# Circuit_Diagram.net
KiCad netlist of a schematic drawn in EAGLE
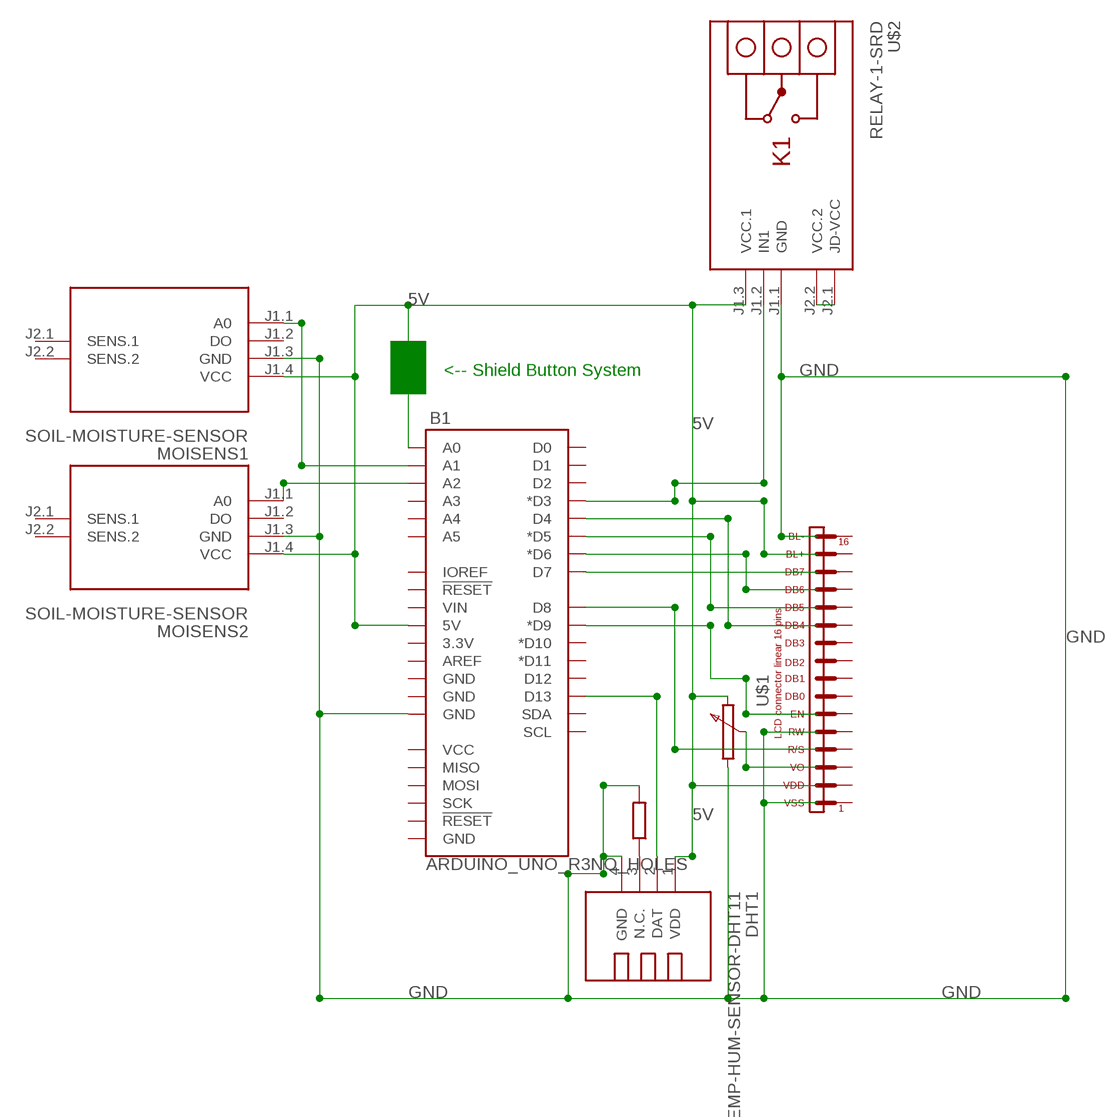
[diagram p0: schematic, sheet 1]

(export (version "E")
  (design (tool "Eeschema 10.0.6"))
  (components
    (comp (ref "B1")
      (value "ARDUINO_UNO_R3NO_HOLES")
      (footprint "eagle-import:ARDUINO_R3_NO_HOLES")
      (libsource (lib "eagle-import") (part "ARDUINO_UNO_R3NO_HOLES"))
    )
    (comp (ref "DHT1")
      (value "TEMP-HUM-SENSOR-DHT11")
      (footprint "eagle-import:TEMP-HUM-SENSOR-DHT11")
      (libsource (lib "eagle-import") (part "TEMP-HUM-SENSOR-DHT11"))
    )
    (comp (ref "MOISENS1")
      (value "SOIL-MOISTURE-SENSOR")
      (footprint "eagle-import:SOIL-MOISTURE-SENSOR")
      (libsource (lib "eagle-import") (part "SOIL-MOISTURE-SENSOR"))
    )
    (comp (ref "MOISENS2")
      (value "SOIL-MOISTURE-SENSOR")
      (footprint "eagle-import:SOIL-MOISTURE-SENSOR")
      (libsource (lib "eagle-import") (part "SOIL-MOISTURE-SENSOR"))
    )
    (comp (ref "U$1")
      (value "-LCD2X16")
      (footprint "eagle-import:CON8X2LCD")
      (libsource (lib "eagle-import") (part "-LCD2X16"))
    )
    (comp (ref "U$2")
      (value "RELAY-1-SRD")
      (footprint "eagle-import:RELAY-1-SRD")
      (libsource (lib "eagle-import") (part "RELAY-1-SRD"))
    )
  )
  (nets
    (net (code "1") (name "/5V") (class "Default")
      (node (ref "B1") (pin "5V") (pinfunction "5V_5V") (pintype "bidirectional"))
      (node (ref "B1") (pin "A0") (pinfunction "A0_A0") (pintype "bidirectional"))
      (node (ref "DHT1") (pin "1") (pinfunction "VDD_1") (pintype "power_in"))
      (node (ref "MOISENS1") (pin "J1.4") (pinfunction "VCC_J1.4") (pintype "power_in"))
      (node (ref "MOISENS2") (pin "J1.4") (pinfunction "VCC_J1.4") (pintype "power_in"))
      (node (ref "U$2") (pin "J1.3") (pinfunction "VCC.1_J1.3") (pintype "power_in"))
    )
    (net (code "2") (name "/GND") (class "Default")
      (node (ref "B1") (pin "GND@2") (pinfunction "GND_GND@2") (pintype "bidirectional"))
      (node (ref "DHT1") (pin "4") (pinfunction "GND_4") (pintype "power_in"))
      (node (ref "MOISENS1") (pin "J1.3") (pinfunction "GND_J1.3") (pintype "power_in"))
      (node (ref "MOISENS2") (pin "J1.3") (pinfunction "GND_J1.3") (pintype "power_in"))
      (node (ref "U$2") (pin "J1.1") (pinfunction "GND_J1.1") (pintype "power_in"))
    )
    (net (code "3") (name "Net-(B1-*D3)") (class "Default")
      (node (ref "B1") (pin "D3") (pinfunction "*D3_D3") (pintype "bidirectional"))
      (node (ref "U$2") (pin "J1.2") (pinfunction "IN1_J1.2") (pintype "bidirectional"))
    )
    (net (code "4") (name "Net-(DHT1-DAT)") (class "Default")
      (node (ref "B1") (pin "D13") (pinfunction "D13_D13") (pintype "bidirectional"))
      (node (ref "DHT1") (pin "2") (pinfunction "DAT_2") (pintype "bidirectional"))
    )
    (net (code "5") (name "Net-(MOISENS1-A0)") (class "Default")
      (node (ref "B1") (pin "A1") (pinfunction "A1_A1") (pintype "bidirectional"))
      (node (ref "MOISENS1") (pin "J1.1") (pinfunction "A0_J1.1") (pintype "bidirectional"))
    )
    (net (code "6") (name "Net-(MOISENS2-A0)") (class "Default")
      (node (ref "B1") (pin "A2") (pinfunction "A2_A2") (pintype "bidirectional"))
      (node (ref "MOISENS2") (pin "J1.1") (pinfunction "A0_J1.1") (pintype "bidirectional"))
    )
    (net (code "7") (name "Net-(U$2-JD-VCC)") (class "Default")
      (node (ref "U$2") (pin "J2.1") (pinfunction "JD-VCC_J2.1") (pintype "bidirectional"))
      (node (ref "U$2") (pin "J2.2") (pinfunction "VCC.2_J2.2") (pintype "power_in"))
    )
    (net (code "8") (name "unconnected-(B1-*D5-PadD5)") (class "Default")
      (node (ref "B1") (pin "D5") (pinfunction "*D5_D5") (pintype "bidirectional"))
    )
    (net (code "9") (name "unconnected-(B1-*D6-PadD6)") (class "Default")
      (node (ref "B1") (pin "D6") (pinfunction "*D6_D6") (pintype "bidirectional"))
    )
    (net (code "10") (name "unconnected-(B1-*D9-PadD9)") (class "Default")
      (node (ref "B1") (pin "D9") (pinfunction "*D9_D9") (pintype "bidirectional"))
    )
    (net (code "11") (name "unconnected-(B1-*D10-PadD10)") (class "Default")
      (node (ref "B1") (pin "D10") (pinfunction "*D10_D10") (pintype "bidirectional"))
    )
    (net (code "12") (name "unconnected-(B1-*D11-PadD11)") (class "Default")
      (node (ref "B1") (pin "D11") (pinfunction "*D11_D11") (pintype "bidirectional"))
    )
    (net (code "13") (name "unconnected-(B1-GND-PadGND@1)") (class "Default")
      (node (ref "B1") (pin "GND@1") (pinfunction "GND_GND@1") (pintype "bidirectional"))
    )
    (net (code "14") (name "unconnected-(B1-GND-PadGND@3)") (class "Default")
      (node (ref "B1") (pin "GND@3") (pinfunction "GND_GND@3") (pintype "bidirectional"))
    )
    (net (code "15") (name "unconnected-(B1-GND-PadGND@4)") (class "Default")
      (node (ref "B1") (pin "GND@4") (pinfunction "GND_GND@4") (pintype "bidirectional"))
    )
    (net (code "16") (name "unconnected-(B1-Pad3.3V)") (class "Default")
      (node (ref "B1") (pin "3.3V") (pinfunction "3.3V_3.3V") (pintype "bidirectional"))
    )
    (net (code "17") (name "unconnected-(B1-PadA3)") (class "Default")
      (node (ref "B1") (pin "A3") (pinfunction "A3_A3") (pintype "bidirectional"))
    )
    (net (code "18") (name "unconnected-(B1-PadA4)") (class "Default")
      (node (ref "B1") (pin "A4") (pinfunction "A4_A4") (pintype "bidirectional"))
    )
    (net (code "19") (name "unconnected-(B1-PadA5)") (class "Default")
      (node (ref "B1") (pin "A5") (pinfunction "A5_A5") (pintype "bidirectional"))
    )
    (net (code "20") (name "unconnected-(B1-PadAREF)") (class "Default")
      (node (ref "B1") (pin "AREF") (pinfunction "AREF_AREF") (pintype "bidirectional"))
    )
    (net (code "21") (name "unconnected-(B1-PadD0)") (class "Default")
      (node (ref "B1") (pin "D0") (pinfunction "D0_D0") (pintype "bidirectional"))
    )
    (net (code "22") (name "unconnected-(B1-PadD1)") (class "Default")
      (node (ref "B1") (pin "D1") (pinfunction "D1_D1") (pintype "bidirectional"))
    )
    (net (code "23") (name "unconnected-(B1-PadD2)") (class "Default")
      (node (ref "B1") (pin "D2") (pinfunction "D2_D2") (pintype "bidirectional"))
    )
    (net (code "24") (name "unconnected-(B1-PadD4)") (class "Default")
      (node (ref "B1") (pin "D4") (pinfunction "D4_D4") (pintype "bidirectional"))
    )
    (net (code "25") (name "unconnected-(B1-PadD7)") (class "Default")
      (node (ref "B1") (pin "D7") (pinfunction "D7_D7") (pintype "bidirectional"))
    )
    (net (code "26") (name "unconnected-(B1-PadD8)") (class "Default")
      (node (ref "B1") (pin "D8") (pinfunction "D8_D8") (pintype "bidirectional"))
    )
    (net (code "27") (name "unconnected-(B1-PadD12)") (class "Default")
      (node (ref "B1") (pin "D12") (pinfunction "D12_D12") (pintype "bidirectional"))
    )
    (net (code "28") (name "unconnected-(B1-PadIOREF)") (class "Default")
      (node (ref "B1") (pin "IOREF") (pinfunction "IOREF_IOREF") (pintype "bidirectional"))
    )
    (net (code "29") (name "unconnected-(B1-PadMISO)") (class "Default")
      (node (ref "B1") (pin "MISO") (pinfunction "MISO_MISO") (pintype "bidirectional"))
    )
    (net (code "30") (name "unconnected-(B1-PadMOSI)") (class "Default")
      (node (ref "B1") (pin "MOSI") (pinfunction "MOSI_MOSI") (pintype "bidirectional"))
    )
    (net (code "31") (name "unconnected-(B1-PadSCK)") (class "Default")
      (node (ref "B1") (pin "SCK") (pinfunction "SCK_SCK") (pintype "bidirectional"))
    )
    (net (code "32") (name "unconnected-(B1-PadSCL)") (class "Default")
      (node (ref "B1") (pin "SCL") (pinfunction "SCL_SCL") (pintype "bidirectional"))
    )
    (net (code "33") (name "unconnected-(B1-PadSDA)") (class "Default")
      (node (ref "B1") (pin "SDA") (pinfunction "SDA_SDA") (pintype "bidirectional"))
    )
    (net (code "34") (name "unconnected-(B1-PadVCC)") (class "Default")
      (node (ref "B1") (pin "VCC") (pinfunction "VCC_VCC") (pintype "bidirectional"))
    )
    (net (code "35") (name "unconnected-(B1-PadVIN)") (class "Default")
      (node (ref "B1") (pin "VIN") (pinfunction "VIN_VIN") (pintype "bidirectional"))
    )
    (net (code "36") (name "unconnected-(B1-~{RESET}-PadRESET@1)") (class "Default")
      (node (ref "B1") (pin "RESET@1") (pinfunction "~{RESET}_RESET@1") (pintype "bidirectional"))
    )
    (net (code "37") (name "unconnected-(B1-~{RESET}-PadRESET@2)") (class "Default")
      (node (ref "B1") (pin "RESET@2") (pinfunction "~{RESET}_RESET@2") (pintype "bidirectional"))
    )
    (net (code "38") (name "unconnected-(DHT1-N.C.-Pad3)") (class "Default")
      (node (ref "DHT1") (pin "3") (pinfunction "N.C._3") (pintype "passive"))
    )
    (net (code "39") (name "unconnected-(MOISENS1-DO-PadJ1.2)") (class "Default")
      (node (ref "MOISENS1") (pin "J1.2") (pinfunction "DO_J1.2") (pintype "output"))
    )
    (net (code "40") (name "unconnected-(MOISENS1-SENS.1-PadJ2.1)") (class "Default")
      (node (ref "MOISENS1") (pin "J2.1") (pinfunction "SENS.1_J2.1") (pintype "bidirectional"))
    )
    (net (code "41") (name "unconnected-(MOISENS1-SENS.2-PadJ2.2)") (class "Default")
      (node (ref "MOISENS1") (pin "J2.2") (pinfunction "SENS.2_J2.2") (pintype "bidirectional"))
    )
    (net (code "42") (name "unconnected-(MOISENS2-DO-PadJ1.2)") (class "Default")
      (node (ref "MOISENS2") (pin "J1.2") (pinfunction "DO_J1.2") (pintype "output"))
    )
    (net (code "43") (name "unconnected-(MOISENS2-SENS.1-PadJ2.1)") (class "Default")
      (node (ref "MOISENS2") (pin "J2.1") (pinfunction "SENS.1_J2.1") (pintype "bidirectional"))
    )
    (net (code "44") (name "unconnected-(MOISENS2-SENS.2-PadJ2.2)") (class "Default")
      (node (ref "MOISENS2") (pin "J2.2") (pinfunction "SENS.2_J2.2") (pintype "bidirectional"))
    )
    (net (code "45") (name "unconnected-(U$1-BKL+-PadP$15)") (class "Default")
      (node (ref "U$1") (pin "P$15") (pinfunction "BKL+_P$15") (pintype "passive"))
    )
    (net (code "46") (name "unconnected-(U$1-BKL--PadP$16)") (class "Default")
      (node (ref "U$1") (pin "P$16") (pinfunction "BKL-_P$16") (pintype "passive"))
    )
    (net (code "47") (name "unconnected-(U$1-DB0-PadP$7)") (class "Default")
      (node (ref "U$1") (pin "P$7") (pinfunction "DB0_P$7") (pintype "passive"))
    )
    (net (code "48") (name "unconnected-(U$1-DB1-PadP$8)") (class "Default")
      (node (ref "U$1") (pin "P$8") (pinfunction "DB1_P$8") (pintype "passive"))
    )
    (net (code "49") (name "unconnected-(U$1-DB2-PadP$9)") (class "Default")
      (node (ref "U$1") (pin "P$9") (pinfunction "DB2_P$9") (pintype "passive"))
    )
    (net (code "50") (name "unconnected-(U$1-DB3-PadP$10)") (class "Default")
      (node (ref "U$1") (pin "P$10") (pinfunction "DB3_P$10") (pintype "passive"))
    )
    (net (code "51") (name "unconnected-(U$1-DB4-PadP$11)") (class "Default")
      (node (ref "U$1") (pin "P$11") (pinfunction "DB4_P$11") (pintype "passive"))
    )
    (net (code "52") (name "unconnected-(U$1-DB5-PadP$12)") (class "Default")
      (node (ref "U$1") (pin "P$12") (pinfunction "DB5_P$12") (pintype "passive"))
    )
    (net (code "53") (name "unconnected-(U$1-DB6-PadP$13)") (class "Default")
      (node (ref "U$1") (pin "P$13") (pinfunction "DB6_P$13") (pintype "passive"))
    )
    (net (code "54") (name "unconnected-(U$1-DB7-PadP$14)") (class "Default")
      (node (ref "U$1") (pin "P$14") (pinfunction "DB7_P$14") (pintype "passive"))
    )
    (net (code "55") (name "unconnected-(U$1-EN-PadP$6)") (class "Default")
      (node (ref "U$1") (pin "P$6") (pinfunction "EN_P$6") (pintype "passive"))
    )
    (net (code "56") (name "unconnected-(U$1-RW-PadP$4)") (class "Default")
      (node (ref "U$1") (pin "P$4") (pinfunction "RW_P$4") (pintype "passive"))
    )
    (net (code "57") (name "unconnected-(U$1-R{slash}S-PadP$5)") (class "Default")
      (node (ref "U$1") (pin "P$5") (pinfunction "R/S_P$5") (pintype "passive"))
    )
    (net (code "58") (name "unconnected-(U$1-V0-PadP$3)") (class "Default")
      (node (ref "U$1") (pin "P$3") (pinfunction "V0_P$3") (pintype "passive"))
    )
    (net (code "59") (name "unconnected-(U$1-VDD-PadP$2)") (class "Default")
      (node (ref "U$1") (pin "P$2") (pinfunction "VDD_P$2") (pintype "passive"))
    )
    (net (code "60") (name "unconnected-(U$1-VSS-PadP$1)") (class "Default")
      (node (ref "U$1") (pin "P$1") (pinfunction "VSS_P$1") (pintype "passive"))
    )
  )
)
